# xenium-programmer-rpi.net
KiCad netlist of a schematic drawn in EAGLE
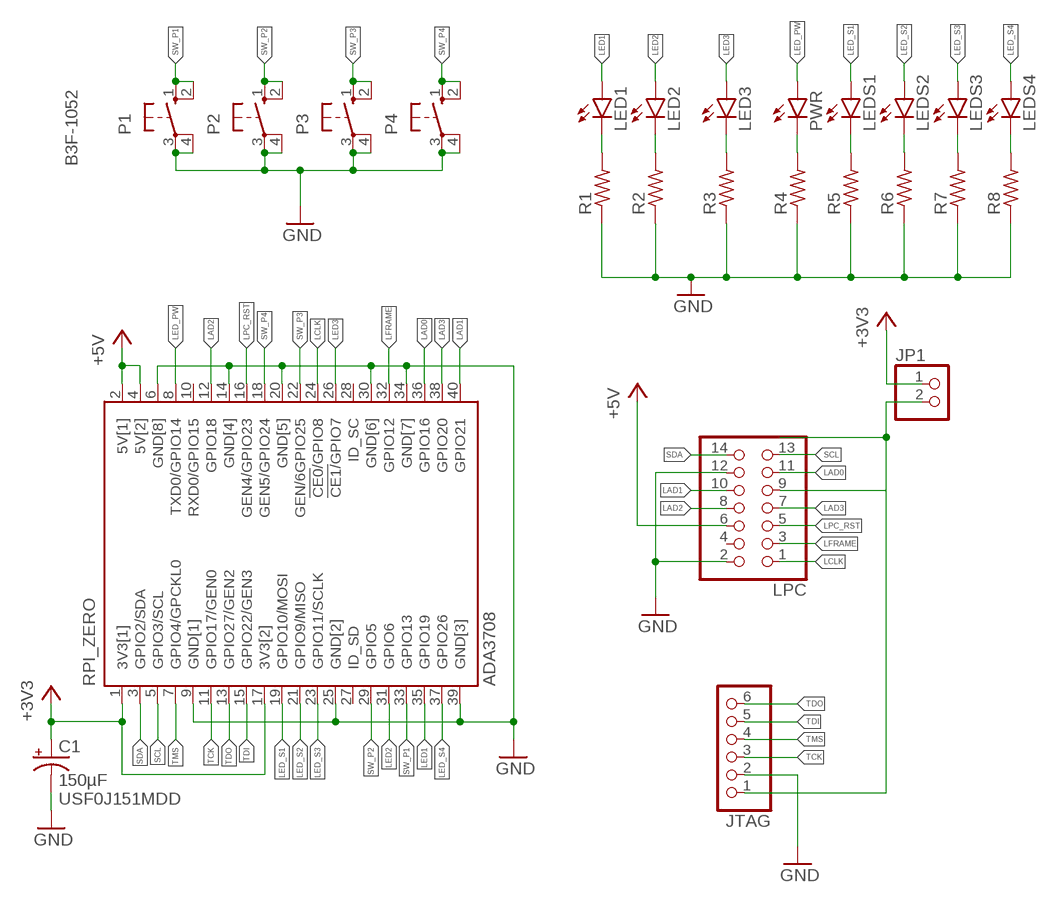
[diagram p0: schematic, sheet 1]

(export (version "E")
  (design (tool "Eeschema 10.0.6"))
  (components
    (comp (ref "C1")
      (value "150µF")
      (footprint "eagle-import:E3,5-8")
      (libsource (lib "eagle-import") (part "CPOL-USE3.5-8"))
    )
    (comp (ref "JP1")
      (value "PINHD-1X2")
      (footprint "eagle-import:1X02")
      (libsource (lib "eagle-import") (part "PINHD-1X2"))
    )
    (comp (ref "JTAG")
      (value "PINHD-1X6")
      (footprint "eagle-import:1X06")
      (libsource (lib "eagle-import") (part "PINHD-1X6"))
    )
    (comp (ref "LED1")
      (value "LEDCHIPLED_1206")
      (footprint "eagle-import:CHIPLED_1206")
      (libsource (lib "eagle-import") (part "LEDCHIPLED_1206"))
    )
    (comp (ref "LED2")
      (value "LEDCHIPLED_1206")
      (footprint "eagle-import:CHIPLED_1206")
      (libsource (lib "eagle-import") (part "LEDCHIPLED_1206"))
    )
    (comp (ref "LED3")
      (value "LEDCHIPLED_1206")
      (footprint "eagle-import:CHIPLED_1206")
      (libsource (lib "eagle-import") (part "LEDCHIPLED_1206"))
    )
    (comp (ref "LEDS1")
      (value "LEDCHIPLED_1206")
      (footprint "eagle-import:CHIPLED_1206")
      (libsource (lib "eagle-import") (part "LEDCHIPLED_1206"))
    )
    (comp (ref "LEDS2")
      (value "LEDCHIPLED_1206")
      (footprint "eagle-import:CHIPLED_1206")
      (libsource (lib "eagle-import") (part "LEDCHIPLED_1206"))
    )
    (comp (ref "LEDS3")
      (value "LEDCHIPLED_1206")
      (footprint "eagle-import:CHIPLED_1206")
      (libsource (lib "eagle-import") (part "LEDCHIPLED_1206"))
    )
    (comp (ref "LEDS4")
      (value "LEDCHIPLED_1206")
      (footprint "eagle-import:CHIPLED_1206")
      (libsource (lib "eagle-import") (part "LEDCHIPLED_1206"))
    )
    (comp (ref "LPC")
      (value "PINHD-2X7")
      (footprint "eagle-import:2X07")
      (libsource (lib "eagle-import") (part "PINHD-2X7"))
    )
    (comp (ref "P1")
      (value "B3F-1052")
      (footprint "eagle-import:B3F-10XX")
      (fields (field (name "MF") "Omron"))
      (libsource (lib "eagle-import") (part "B3F-1052"))
    )
    (comp (ref "P2")
      (value "B3F-1052")
      (footprint "eagle-import:B3F-10XX")
      (fields (field (name "MF") "Omron"))
      (libsource (lib "eagle-import") (part "B3F-1052"))
    )
    (comp (ref "P3")
      (value "B3F-1052")
      (footprint "eagle-import:B3F-10XX")
      (fields (field (name "MF") "Omron"))
      (libsource (lib "eagle-import") (part "B3F-1052"))
    )
    (comp (ref "P4")
      (value "B3F-1052")
      (footprint "eagle-import:B3F-10XX")
      (fields (field (name "MF") "Omron"))
      (libsource (lib "eagle-import") (part "B3F-1052"))
    )
    (comp (ref "PWR")
      (value "LEDCHIPLED_1206")
      (footprint "eagle-import:CHIPLED_1206")
      (libsource (lib "eagle-import") (part "LEDCHIPLED_1206"))
    )
    (comp (ref "R1")
      (value "R-US_R1206")
      (footprint "eagle-import:R1206")
      (libsource (lib "eagle-import") (part "R-US_R1206"))
    )
    (comp (ref "R2")
      (value "R-US_R1206")
      (footprint "eagle-import:R1206")
      (libsource (lib "eagle-import") (part "R-US_R1206"))
    )
    (comp (ref "R3")
      (value "R-US_R1206")
      (footprint "eagle-import:R1206")
      (libsource (lib "eagle-import") (part "R-US_R1206"))
    )
    (comp (ref "R4")
      (value "R-US_R1206")
      (footprint "eagle-import:R1206")
      (libsource (lib "eagle-import") (part "R-US_R1206"))
    )
    (comp (ref "R5")
      (value "R-US_R1206")
      (footprint "eagle-import:R1206")
      (libsource (lib "eagle-import") (part "R-US_R1206"))
    )
    (comp (ref "R6")
      (value "R-US_R1206")
      (footprint "eagle-import:R1206")
      (libsource (lib "eagle-import") (part "R-US_R1206"))
    )
    (comp (ref "R7")
      (value "R-US_R1206")
      (footprint "eagle-import:R1206")
      (libsource (lib "eagle-import") (part "R-US_R1206"))
    )
    (comp (ref "R8")
      (value "R-US_R1206")
      (footprint "eagle-import:R1206")
      (libsource (lib "eagle-import") (part "R-US_R1206"))
    )
    (comp (ref "RPI_ZERO")
      (value "ADA3708")
      (footprint "eagle-import:ADA3708_RPI-ZERO")
      (fields (field (name "MF") "Raspberry Pi"))
      (libsource (lib "eagle-import") (part "ADA3708"))
    )
  )
  (nets
    (net (code "1") (name "+3V3") (class "Default")
      (node (ref "C1") (pin "+") (pinfunction "+_+") (pintype "passive"))
      (node (ref "JP1") (pin "1") (pinfunction "1_1") (pintype "passive"))
      (node (ref "RPI_ZERO") (pin "1") (pinfunction "3V3[1]_1") (pintype "power_in"))
      (node (ref "RPI_ZERO") (pin "17") (pinfunction "3V3[2]_17") (pintype "power_in"))
    )
    (net (code "2") (name "+5V") (class "Default")
      (node (ref "LPC") (pin "6") (pinfunction "6_6") (pintype "passive"))
      (node (ref "RPI_ZERO") (pin "2") (pinfunction "5V[1]_2") (pintype "power_in"))
      (node (ref "RPI_ZERO") (pin "4") (pinfunction "5V[2]_4") (pintype "power_in"))
    )
    (net (code "3") (name "GND") (class "Default")
      (node (ref "C1") (pin "-") (pinfunction "-_-") (pintype "passive"))
      (node (ref "JTAG") (pin "2") (pinfunction "2_2") (pintype "passive"))
      (node (ref "LPC") (pin "12") (pinfunction "12_12") (pintype "passive"))
      (node (ref "LPC") (pin "2") (pinfunction "2_2") (pintype "passive"))
      (node (ref "P1") (pin "3") (pinfunction "P_3") (pintype "passive"))
      (node (ref "P1") (pin "4") (pinfunction "P1_4") (pintype "passive"))
      (node (ref "P2") (pin "3") (pinfunction "P_3") (pintype "passive"))
      (node (ref "P2") (pin "4") (pinfunction "P1_4") (pintype "passive"))
      (node (ref "P3") (pin "3") (pinfunction "P_3") (pintype "passive"))
      (node (ref "P3") (pin "4") (pinfunction "P1_4") (pintype "passive"))
      (node (ref "P4") (pin "3") (pinfunction "P_3") (pintype "passive"))
      (node (ref "P4") (pin "4") (pinfunction "P1_4") (pintype "passive"))
      (node (ref "R1") (pin "1") (pinfunction "1_1") (pintype "passive"))
      (node (ref "R2") (pin "1") (pinfunction "1_1") (pintype "passive"))
      (node (ref "R3") (pin "1") (pinfunction "1_1") (pintype "passive"))
      (node (ref "R4") (pin "1") (pinfunction "1_1") (pintype "passive"))
      (node (ref "R5") (pin "1") (pinfunction "1_1") (pintype "passive"))
      (node (ref "R6") (pin "1") (pinfunction "1_1") (pintype "passive"))
      (node (ref "R7") (pin "1") (pinfunction "1_1") (pintype "passive"))
      (node (ref "R8") (pin "1") (pinfunction "1_1") (pintype "passive"))
      (node (ref "RPI_ZERO") (pin "14") (pinfunction "GND[4]_14") (pintype "power_in"))
      (node (ref "RPI_ZERO") (pin "20") (pinfunction "GND[5]_20") (pintype "power_in"))
      (node (ref "RPI_ZERO") (pin "25") (pinfunction "GND[2]_25") (pintype "power_in"))
      (node (ref "RPI_ZERO") (pin "30") (pinfunction "GND[6]_30") (pintype "power_in"))
      (node (ref "RPI_ZERO") (pin "34") (pinfunction "GND[7]_34") (pintype "power_in"))
      (node (ref "RPI_ZERO") (pin "39") (pinfunction "GND[3]_39") (pintype "power_in"))
      (node (ref "RPI_ZERO") (pin "6") (pinfunction "GND[8]_6") (pintype "power_in"))
      (node (ref "RPI_ZERO") (pin "9") (pinfunction "GND[1]_9") (pintype "power_in"))
    )
    (net (code "4") (name "LAD0") (class "Default")
      (node (ref "LPC") (pin "11") (pinfunction "11_11") (pintype "passive"))
      (node (ref "RPI_ZERO") (pin "36") (pinfunction "GPIO16_36") (pintype "bidirectional"))
    )
    (net (code "5") (name "LAD1") (class "Default")
      (node (ref "LPC") (pin "10") (pinfunction "10_10") (pintype "passive"))
      (node (ref "RPI_ZERO") (pin "40") (pinfunction "GPIO21_40") (pintype "bidirectional"))
    )
    (net (code "6") (name "LAD2") (class "Default")
      (node (ref "LPC") (pin "8") (pinfunction "8_8") (pintype "passive"))
      (node (ref "RPI_ZERO") (pin "12") (pinfunction "GPIO18_12") (pintype "bidirectional"))
    )
    (net (code "7") (name "LAD3") (class "Default")
      (node (ref "LPC") (pin "7") (pinfunction "7_7") (pintype "passive"))
      (node (ref "RPI_ZERO") (pin "38") (pinfunction "GPIO20_38") (pintype "bidirectional"))
    )
    (net (code "8") (name "LCLK") (class "Default")
      (node (ref "LPC") (pin "1") (pinfunction "1_1") (pintype "passive"))
      (node (ref "RPI_ZERO") (pin "24") (pinfunction "~{CE0}/GPIO8_24") (pintype "bidirectional"))
    )
    (net (code "9") (name "LED1") (class "Default")
      (node (ref "LED1") (pin "A") (pinfunction "A_A") (pintype "passive"))
      (node (ref "RPI_ZERO") (pin "35") (pinfunction "GPIO19_35") (pintype "bidirectional"))
    )
    (net (code "10") (name "LED2") (class "Default")
      (node (ref "LED2") (pin "A") (pinfunction "A_A") (pintype "passive"))
      (node (ref "RPI_ZERO") (pin "31") (pinfunction "GPIO6_31") (pintype "bidirectional"))
    )
    (net (code "11") (name "LED3") (class "Default")
      (node (ref "LED3") (pin "A") (pinfunction "A_A") (pintype "passive"))
      (node (ref "RPI_ZERO") (pin "26") (pinfunction "~{CE1/}GPIO7_26") (pintype "bidirectional"))
    )
    (net (code "12") (name "LED_PW") (class "Default")
      (node (ref "PWR") (pin "A") (pinfunction "A_A") (pintype "passive"))
      (node (ref "RPI_ZERO") (pin "8") (pinfunction "TXD0/GPIO14_8") (pintype "bidirectional"))
    )
    (net (code "13") (name "LED_S1") (class "Default")
      (node (ref "LEDS1") (pin "A") (pinfunction "A_A") (pintype "passive"))
      (node (ref "RPI_ZERO") (pin "19") (pinfunction "GPIO10/MOSI_19") (pintype "bidirectional"))
    )
    (net (code "14") (name "LED_S2") (class "Default")
      (node (ref "LEDS2") (pin "A") (pinfunction "A_A") (pintype "passive"))
      (node (ref "RPI_ZERO") (pin "21") (pinfunction "GPIO9/MISO_21") (pintype "bidirectional"))
    )
    (net (code "15") (name "LED_S3") (class "Default")
      (node (ref "LEDS3") (pin "A") (pinfunction "A_A") (pintype "passive"))
      (node (ref "RPI_ZERO") (pin "23") (pinfunction "GPIO11/SCLK_23") (pintype "bidirectional"))
    )
    (net (code "16") (name "LED_S4") (class "Default")
      (node (ref "LEDS4") (pin "A") (pinfunction "A_A") (pintype "passive"))
      (node (ref "RPI_ZERO") (pin "37") (pinfunction "GPIO26_37") (pintype "bidirectional"))
    )
    (net (code "17") (name "LFRAME") (class "Default")
      (node (ref "LPC") (pin "3") (pinfunction "3_3") (pintype "passive"))
      (node (ref "RPI_ZERO") (pin "32") (pinfunction "GPIO12_32") (pintype "bidirectional"))
    )
    (net (code "18") (name "LPC_RST") (class "Default")
      (node (ref "LPC") (pin "5") (pinfunction "5_5") (pintype "passive"))
      (node (ref "RPI_ZERO") (pin "16") (pinfunction "GEN4/GPIO23_16") (pintype "bidirectional"))
    )
    (net (code "19") (name "Net-(JP1-Pad2)") (class "Default")
      (node (ref "JP1") (pin "2") (pinfunction "2_2") (pintype "passive"))
      (node (ref "JTAG") (pin "1") (pinfunction "1_1") (pintype "passive"))
      (node (ref "LPC") (pin "9") (pinfunction "9_9") (pintype "passive"))
    )
    (net (code "20") (name "Net-(LED1-PadC)") (class "Default")
      (node (ref "LED1") (pin "C") (pinfunction "C_C") (pintype "passive"))
      (node (ref "R1") (pin "2") (pinfunction "2_2") (pintype "passive"))
    )
    (net (code "21") (name "Net-(LED2-PadC)") (class "Default")
      (node (ref "LED2") (pin "C") (pinfunction "C_C") (pintype "passive"))
      (node (ref "R2") (pin "2") (pinfunction "2_2") (pintype "passive"))
    )
    (net (code "22") (name "Net-(LED3-PadC)") (class "Default")
      (node (ref "LED3") (pin "C") (pinfunction "C_C") (pintype "passive"))
      (node (ref "R3") (pin "2") (pinfunction "2_2") (pintype "passive"))
    )
    (net (code "23") (name "Net-(LEDS1-PadC)") (class "Default")
      (node (ref "LEDS1") (pin "C") (pinfunction "C_C") (pintype "passive"))
      (node (ref "R5") (pin "2") (pinfunction "2_2") (pintype "passive"))
    )
    (net (code "24") (name "Net-(LEDS2-PadC)") (class "Default")
      (node (ref "LEDS2") (pin "C") (pinfunction "C_C") (pintype "passive"))
      (node (ref "R6") (pin "2") (pinfunction "2_2") (pintype "passive"))
    )
    (net (code "25") (name "Net-(LEDS3-PadC)") (class "Default")
      (node (ref "LEDS3") (pin "C") (pinfunction "C_C") (pintype "passive"))
      (node (ref "R7") (pin "2") (pinfunction "2_2") (pintype "passive"))
    )
    (net (code "26") (name "Net-(LEDS4-PadC)") (class "Default")
      (node (ref "LEDS4") (pin "C") (pinfunction "C_C") (pintype "passive"))
      (node (ref "R8") (pin "2") (pinfunction "2_2") (pintype "passive"))
    )
    (net (code "27") (name "Net-(PWR-PadC)") (class "Default")
      (node (ref "PWR") (pin "C") (pinfunction "C_C") (pintype "passive"))
      (node (ref "R4") (pin "2") (pinfunction "2_2") (pintype "passive"))
    )
    (net (code "28") (name "SCL") (class "Default")
      (node (ref "LPC") (pin "13") (pinfunction "13_13") (pintype "passive"))
      (node (ref "RPI_ZERO") (pin "5") (pinfunction "GPIO3/SCL_5") (pintype "bidirectional"))
    )
    (net (code "29") (name "SDA") (class "Default")
      (node (ref "LPC") (pin "14") (pinfunction "14_14") (pintype "passive"))
      (node (ref "RPI_ZERO") (pin "3") (pinfunction "GPIO2/SDA_3") (pintype "bidirectional"))
    )
    (net (code "30") (name "SW_P1") (class "Default")
      (node (ref "P1") (pin "1") (pinfunction "S_1") (pintype "passive"))
      (node (ref "P1") (pin "2") (pinfunction "S1_2") (pintype "passive"))
      (node (ref "RPI_ZERO") (pin "33") (pinfunction "GPIO13_33") (pintype "bidirectional"))
    )
    (net (code "31") (name "SW_P2") (class "Default")
      (node (ref "P2") (pin "1") (pinfunction "S_1") (pintype "passive"))
      (node (ref "P2") (pin "2") (pinfunction "S1_2") (pintype "passive"))
      (node (ref "RPI_ZERO") (pin "29") (pinfunction "GPIO5_29") (pintype "bidirectional"))
    )
    (net (code "32") (name "SW_P3") (class "Default")
      (node (ref "P3") (pin "1") (pinfunction "S_1") (pintype "passive"))
      (node (ref "P3") (pin "2") (pinfunction "S1_2") (pintype "passive"))
      (node (ref "RPI_ZERO") (pin "22") (pinfunction "GEN/6GPIO25_22") (pintype "bidirectional"))
    )
    (net (code "33") (name "SW_P4") (class "Default")
      (node (ref "P4") (pin "1") (pinfunction "S_1") (pintype "passive"))
      (node (ref "P4") (pin "2") (pinfunction "S1_2") (pintype "passive"))
      (node (ref "RPI_ZERO") (pin "18") (pinfunction "GEN5/GPIO24_18") (pintype "bidirectional"))
    )
    (net (code "34") (name "TCK") (class "Default")
      (node (ref "JTAG") (pin "3") (pinfunction "3_3") (pintype "passive"))
      (node (ref "RPI_ZERO") (pin "11") (pinfunction "GPIO17/GEN0_11") (pintype "bidirectional"))
    )
    (net (code "35") (name "TDI") (class "Default")
      (node (ref "JTAG") (pin "5") (pinfunction "5_5") (pintype "passive"))
      (node (ref "RPI_ZERO") (pin "15") (pinfunction "GPIO22/GEN3_15") (pintype "bidirectional"))
    )
    (net (code "36") (name "TDO") (class "Default")
      (node (ref "JTAG") (pin "6") (pinfunction "6_6") (pintype "passive"))
      (node (ref "RPI_ZERO") (pin "13") (pinfunction "GPIO27/GEN2_13") (pintype "bidirectional"))
    )
    (net (code "37") (name "TMS") (class "Default")
      (node (ref "JTAG") (pin "4") (pinfunction "4_4") (pintype "passive"))
      (node (ref "RPI_ZERO") (pin "7") (pinfunction "GPIO4/GPCKL0_7") (pintype "bidirectional"))
    )
    (net (code "38") (name "unconnected-(LPC-Pad4)") (class "Default")
      (node (ref "LPC") (pin "4") (pinfunction "4_4") (pintype "passive"))
    )
    (net (code "39") (name "unconnected-(RPI_ZERO-ID_SC-Pad28)") (class "Default")
      (node (ref "RPI_ZERO") (pin "28") (pinfunction "ID_SC_28") (pintype "bidirectional"))
    )
    (net (code "40") (name "unconnected-(RPI_ZERO-ID_SD-Pad27)") (class "Default")
      (node (ref "RPI_ZERO") (pin "27") (pinfunction "ID_SD_27") (pintype "bidirectional"))
    )
    (net (code "41") (name "unconnected-(RPI_ZERO-RXD0{slash}GPIO15-Pad10)") (class "Default")
      (node (ref "RPI_ZERO") (pin "10") (pinfunction "RXD0/GPIO15_10") (pintype "bidirectional"))
    )
  )
)
